# USB_IN.net
KiCad netlist of a schematic drawn in Altium Designer
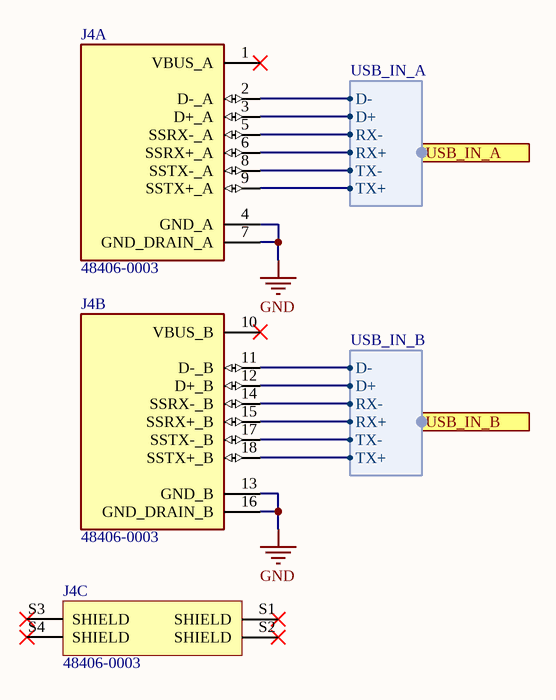
[diagram p0: USB_IN.SchDoc]

(export (version "E")
  (design (tool "Eeschema 10.0.6"))
  (components
    (comp (ref "J4")
      (value "48406-0003")
      (footprint "MOLEX_48406")
      (fields (field (name "MF") "Molex"))
      (libsource (lib "KVM Library") (part "48406-0003"))
    )
  )
  (nets
    (net (code "5") (name "GND") (class "Default")
      (node (ref "J4") (pin "13") (pinfunction "GND_B_13") (pintype "power_in"))
      (node (ref "J4") (pin "16") (pinfunction "GND_DRAIN_B_16") (pintype "power_in"))
      (node (ref "J4") (pin "4") (pinfunction "GND_A_4") (pintype "power_in"))
      (node (ref "J4") (pin "7") (pinfunction "GND_DRAIN_A_7") (pintype "power_in"))
    )
    (net (code "6") (name "unconnected-(J4A-D+_A-Pad3)") (class "Default")
      (node (ref "J4") (pin "3") (pinfunction "D+_A_3") (pintype "bidirectional"))
    )
    (net (code "7") (name "unconnected-(J4A-D-_A-Pad2)") (class "Default")
      (node (ref "J4") (pin "2") (pinfunction "D-_A_2") (pintype "bidirectional"))
    )
    (net (code "8") (name "unconnected-(J4A-SSRX+_A-Pad6)") (class "Default")
      (node (ref "J4") (pin "6") (pinfunction "SSRX+_A_6") (pintype "bidirectional"))
    )
    (net (code "9") (name "unconnected-(J4A-SSRX-_A-Pad5)") (class "Default")
      (node (ref "J4") (pin "5") (pinfunction "SSRX-_A_5") (pintype "bidirectional"))
    )
    (net (code "10") (name "unconnected-(J4A-SSTX+_A-Pad9)") (class "Default")
      (node (ref "J4") (pin "9") (pinfunction "SSTX+_A_9") (pintype "bidirectional"))
    )
    (net (code "11") (name "unconnected-(J4A-SSTX-_A-Pad8)") (class "Default")
      (node (ref "J4") (pin "8") (pinfunction "SSTX-_A_8") (pintype "bidirectional"))
    )
    (net (code "12") (name "unconnected-(J4A-VBUS_A-Pad1)") (class "Default")
      (node (ref "J4") (pin "1") (pinfunction "VBUS_A_1") (pintype "power_in+no_connect"))
    )
    (net (code "13") (name "unconnected-(J4B-D+_B-Pad12)") (class "Default")
      (node (ref "J4") (pin "12") (pinfunction "D+_B_12") (pintype "bidirectional"))
    )
    (net (code "14") (name "unconnected-(J4B-D-_B-Pad11)") (class "Default")
      (node (ref "J4") (pin "11") (pinfunction "D-_B_11") (pintype "bidirectional"))
    )
    (net (code "15") (name "unconnected-(J4B-SSRX+_B-Pad15)") (class "Default")
      (node (ref "J4") (pin "15") (pinfunction "SSRX+_B_15") (pintype "bidirectional"))
    )
    (net (code "16") (name "unconnected-(J4B-SSRX-_B-Pad14)") (class "Default")
      (node (ref "J4") (pin "14") (pinfunction "SSRX-_B_14") (pintype "bidirectional"))
    )
    (net (code "17") (name "unconnected-(J4B-SSTX+_B-Pad18)") (class "Default")
      (node (ref "J4") (pin "18") (pinfunction "SSTX+_B_18") (pintype "bidirectional"))
    )
    (net (code "18") (name "unconnected-(J4B-SSTX-_B-Pad17)") (class "Default")
      (node (ref "J4") (pin "17") (pinfunction "SSTX-_B_17") (pintype "bidirectional"))
    )
    (net (code "19") (name "unconnected-(J4B-VBUS_B-Pad10)") (class "Default")
      (node (ref "J4") (pin "10") (pinfunction "VBUS_B_10") (pintype "power_in+no_connect"))
    )
    (net (code "20") (name "unconnected-(J4C-SHIELD-PadS1)") (class "Default")
      (node (ref "J4") (pin "S1") (pinfunction "SHIELD_S1") (pintype "passive+no_connect"))
    )
    (net (code "21") (name "unconnected-(J4C-SHIELD-PadS2)") (class "Default")
      (node (ref "J4") (pin "S2") (pinfunction "SHIELD_S2") (pintype "passive+no_connect"))
    )
    (net (code "22") (name "unconnected-(J4C-SHIELD-PadS3)") (class "Default")
      (node (ref "J4") (pin "S3") (pinfunction "SHIELD_S3") (pintype "passive+no_connect"))
    )
    (net (code "23") (name "unconnected-(J4C-SHIELD-PadS4)") (class "Default")
      (node (ref "J4") (pin "S4") (pinfunction "SHIELD_S4") (pintype "passive+no_connect"))
    )
  )
)
